# 250100020129x-HW-V2_2.net
KiCad netlist of a schematic drawn in EAGLE
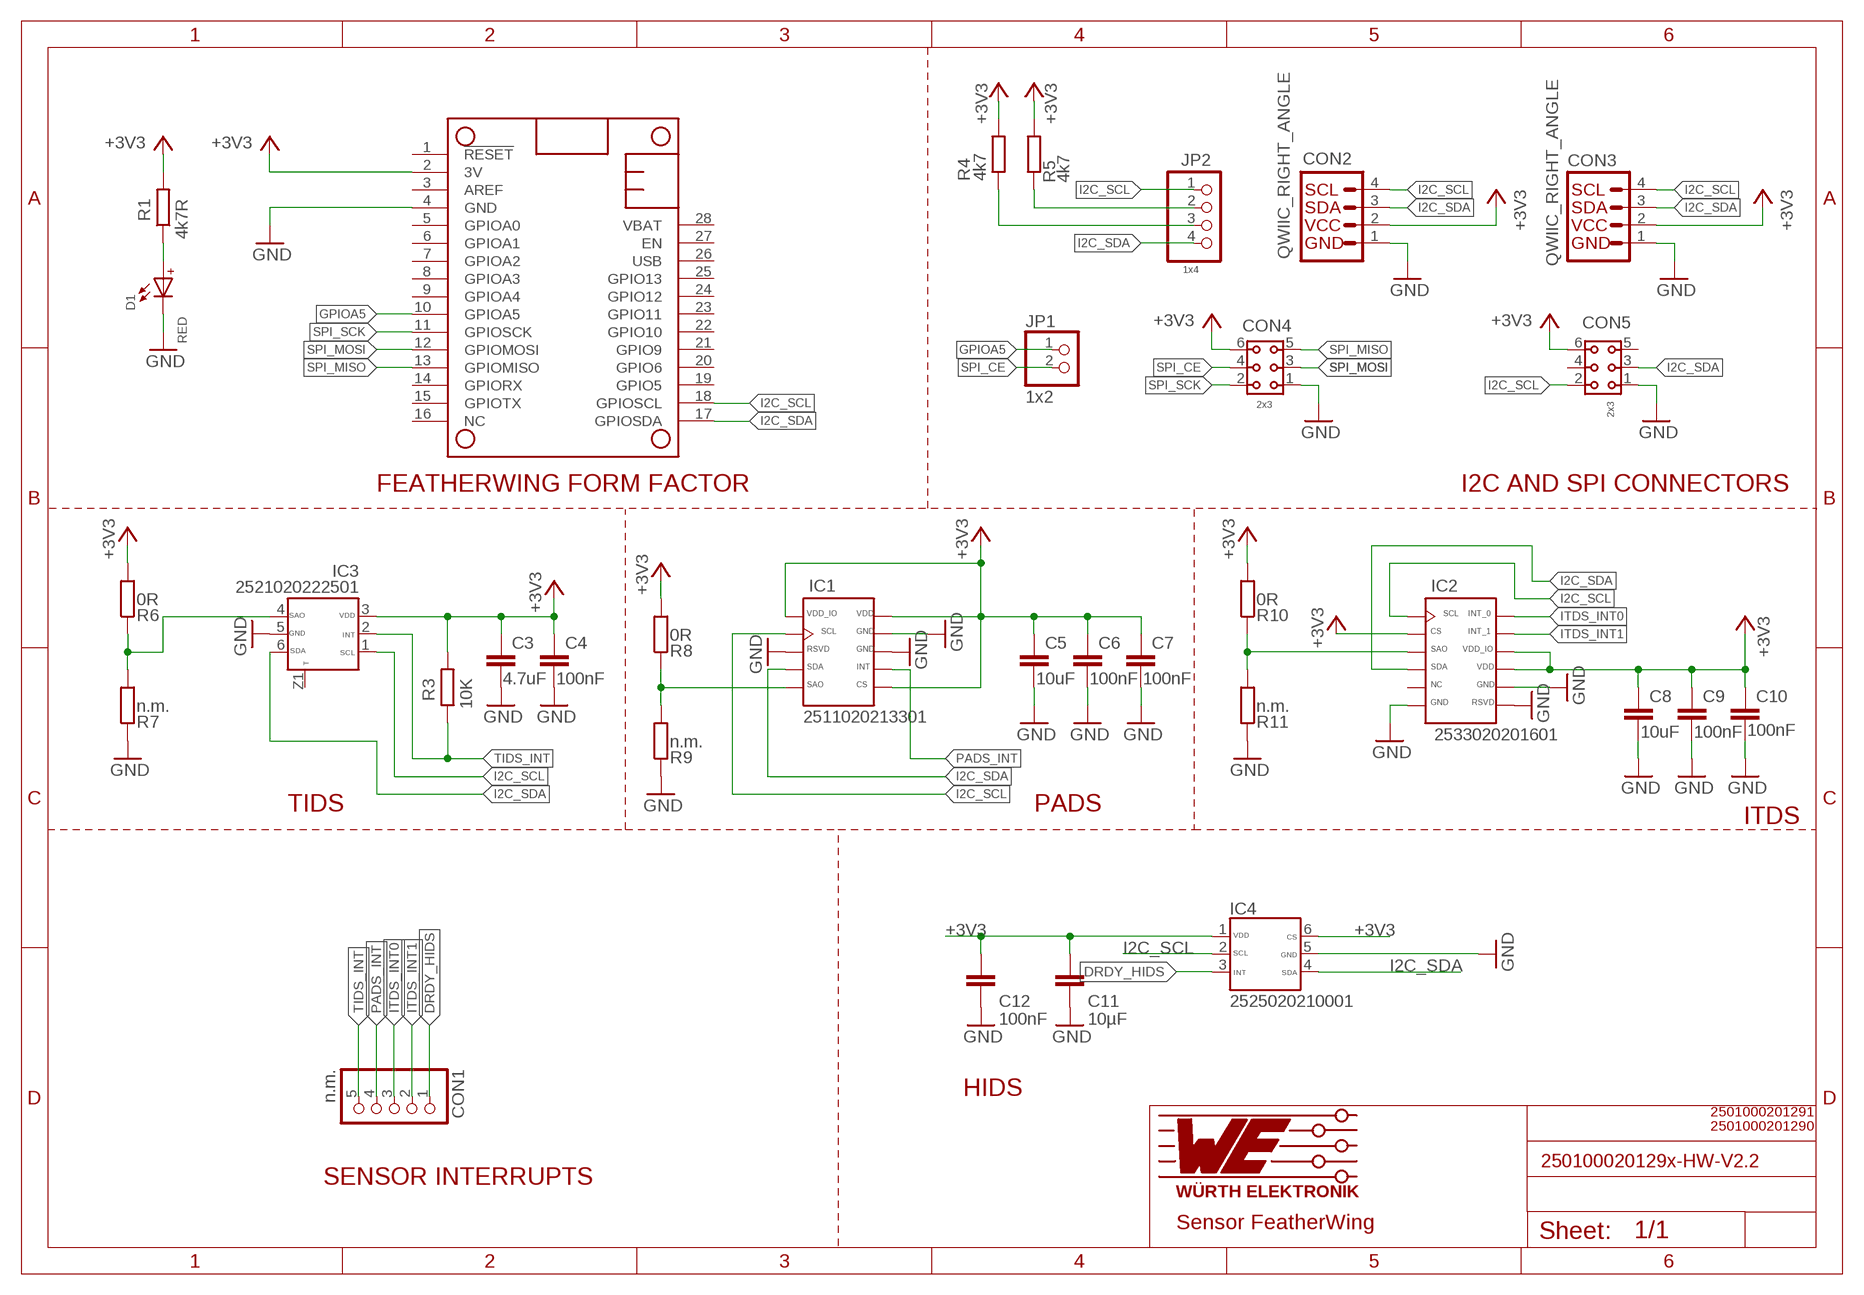
[diagram p0: schematic, sheet 1]

(export (version "E")
  (design (tool "Eeschema 10.0.6"))
  (components
    (comp (ref "C3")
      (value "4.7uF")
      (footprint "eagle-import:C0402_IPC")
      (fields (field (name "MANUFACTURER") "Murata"))
      (libsource (lib "eagle-import") (part "C0402_IPC4,7UF"))
    )
    (comp (ref "C4")
      (value "100nF")
      (footprint "eagle-import:C0402_IPC")
      (fields (field (name "MANUFACTURER") "Yageo"))
      (libsource (lib "eagle-import") (part "C0402_IPC100NF"))
    )
    (comp (ref "C5")
      (value "10uF")
      (footprint "eagle-import:C0402_IPC")
      (fields (field (name "MANUFACTURER") "Murata"))
      (libsource (lib "eagle-import") (part "C0402_IPC10UF"))
    )
    (comp (ref "C6")
      (value "100nF")
      (footprint "eagle-import:C0402_IPC")
      (fields (field (name "MANUFACTURER") "Yageo"))
      (libsource (lib "eagle-import") (part "C0402_IPC100NF"))
    )
    (comp (ref "C7")
      (value "100nF")
      (footprint "eagle-import:C0402_IPC")
      (fields (field (name "MANUFACTURER") "Yageo"))
      (libsource (lib "eagle-import") (part "C0402_IPC100NF"))
    )
    (comp (ref "C8")
      (value "10uF")
      (footprint "eagle-import:C0402_IPC")
      (fields (field (name "MANUFACTURER") "Murata"))
      (libsource (lib "eagle-import") (part "C0402_IPC10UF"))
    )
    (comp (ref "C9")
      (value "100nF")
      (footprint "eagle-import:C0402_IPC")
      (fields (field (name "MANUFACTURER") "Yageo"))
      (libsource (lib "eagle-import") (part "C0402_IPC100NF"))
    )
    (comp (ref "C10")
      (value "100nF")
      (footprint "eagle-import:C0402_IPC")
      (fields (field (name "MANUFACTURER") "Yageo"))
      (libsource (lib "eagle-import") (part "C0402_IPC100NF"))
    )
    (comp (ref "C11")
      (value "10µF")
      (footprint "eagle-import:C0402_IPC")
      (fields (field (name "MANUFACTURER") "Murata"))
      (libsource (lib "eagle-import") (part "C0402_IPC10UF"))
    )
    (comp (ref "C12")
      (value "100nF")
      (footprint "eagle-import:C0402_IPC")
      (fields (field (name "MANUFACTURER") "Yageo"))
      (libsource (lib "eagle-import") (part "C0402_IPC100NF"))
    )
    (comp (ref "CON1")
      (value "n.m.")
      (footprint "eagle-import:1X05_R")
      (fields (field (name "MANUFACTURER") "Würth Elektronik"))
      (libsource (lib "eagle-import") (part "PINHD-1X5/R"))
    )
    (comp (ref "CON2")
      (value "QWIIC_RIGHT_ANGLE")
      (footprint "eagle-import:JST04_1MM_RA")
      (fields (field (name "MANUFACTURER") "JST"))
      (libsource (lib "eagle-import") (part "QWIIC_CONNECTORJS-1MM"))
    )
    (comp (ref "CON3")
      (value "QWIIC_RIGHT_ANGLE")
      (footprint "eagle-import:JST04_1MM_RA")
      (fields (field (name "MANUFACTURER") "JST"))
      (libsource (lib "eagle-import") (part "QWIIC_CONNECTORJS-1MM"))
    )
    (comp (ref "CON4")
      (value "2x3")
      (footprint "eagle-import:613006243121")
      (fields (field (name "MANUFACTURER") "Würth Elektronik") (field (name "COMMENT") "Stick out of PCB"))
      (libsource (lib "eagle-import") (part "6130XX243121_613006243121"))
    )
    (comp (ref "CON5")
      (value "2x3")
      (footprint "eagle-import:613006243121")
      (fields (field (name "MANUFACTURER") "Würth Elektronik") (field (name "COMMENT") "Stick out of PCB"))
      (libsource (lib "eagle-import") (part "6130XX243121_613006243121"))
    )
    (comp (ref "D1")
      (value "RED")
      (footprint "eagle-import:WL-SMSW_1204_A")
      (fields (field (name "MANUFACTURER") "Würth Elektronik"))
      (libsource (lib "eagle-import") (part "WL-SMSW_1204_155124VS73200"))
    )
    (comp (ref "IC1")
      (value "2511020213301")
      (footprint "eagle-import:WSEN-PADS_2511020213301")
      (fields (field (name "MANUFACTURER") "Würth Elektronik"))
      (libsource (lib "eagle-import") (part "WSEN-PADS_2511020213301"))
    )
    (comp (ref "IC2")
      (value "2533020201601")
      (footprint "eagle-import:WSEN-ITDS_2533020201601")
      (fields (field (name "MANUFACTURER") "Würth Elektronik"))
      (libsource (lib "eagle-import") (part "WSEN-ITDS_2533020201601"))
    )
    (comp (ref "IC3")
      (value "2521020222501")
      (footprint "eagle-import:WSEN-TIDS_2521020222501")
      (fields (field (name "MANUFACTURER") "Würth Elektronik"))
      (libsource (lib "eagle-import") (part "WSEN-TIDS_2521020222501"))
    )
    (comp (ref "IC4")
      (value "2525020210001")
      (footprint "eagle-import:WSEN-HIDS_2525020210001")
      (fields (field (name "MANUFACTURER") "Würth Elektronik") (field (name "HEIGHT") "1.0mm"))
      (libsource (lib "eagle-import") (part "WSEN-HIDS_2525020210001"))
    )
    (comp (ref "JP1")
      (value "1x2")
      (footprint "eagle-import:1X02_R")
      (fields (field (name "MANUFACTURER") "Würth Elektronik"))
      (libsource (lib "eagle-import") (part "PINHD-1X2/R"))
    )
    (comp (ref "JP2")
      (value "1x4")
      (footprint "eagle-import:1X04_R")
      (fields (field (name "COMMENT") "2xJumper, 1-2, 3-4") (field (name "MANUFACTURER") "Würth Elektronik"))
      (libsource (lib "eagle-import") (part "PINHD-1X4/R"))
    )
    (comp (ref "MS1")
      (value "FEATHERWING")
      (footprint "eagle-import:FEATHERWING")
      (fields
        (field (name "COMMENT") "header: 1 x 12 & 1 x 16, stackup, pins clean")
        (field (name "MANUFACTURER") "Adafruit")
      )
      (libsource (lib "eagle-import") (part "FEATHERWING"))
    )
    (comp (ref "R1")
      (value "4k7R")
      (footprint "eagle-import:R0402_IPC")
      (fields (field (name "MANUFACTURER") "Yageo"))
      (libsource (lib "eagle-import") (part "R0402_IPC4K7"))
    )
    (comp (ref "R3")
      (value "10K")
      (footprint "eagle-import:R0402_IPC")
      (fields (field (name "MANUFACTURER") "Yageo"))
      (libsource (lib "eagle-import") (part "R0402_IPC10KR"))
    )
    (comp (ref "R4")
      (value "4k7")
      (footprint "eagle-import:R0402_IPC")
      (fields (field (name "MANUFACTURER") "Yageo"))
      (libsource (lib "eagle-import") (part "R0402_IPC4K7"))
    )
    (comp (ref "R5")
      (value "4k7")
      (footprint "eagle-import:R0402_IPC")
      (fields (field (name "MANUFACTURER") "Yageo"))
      (libsource (lib "eagle-import") (part "R0402_IPC4K7"))
    )
    (comp (ref "R6")
      (value "0R")
      (footprint "eagle-import:R0402_IPC")
      (fields (field (name "MANUFACTURER") "Yageo"))
      (libsource (lib "eagle-import") (part "R0402_IPC0R"))
    )
    (comp (ref "R7")
      (value "n.m.")
      (footprint "eagle-import:R0402_IPC")
      (fields (field (name "MANUFACTURER") "Yageo"))
      (libsource (lib "eagle-import") (part "R0402_IPC"))
    )
    (comp (ref "R8")
      (value "0R")
      (footprint "eagle-import:R0402_IPC")
      (fields (field (name "MANUFACTURER") "Yageo"))
      (libsource (lib "eagle-import") (part "R0402_IPC0R"))
    )
    (comp (ref "R9")
      (value "n.m.")
      (footprint "eagle-import:R0402_IPC")
      (fields (field (name "MANUFACTURER") "Yageo"))
      (libsource (lib "eagle-import") (part "R0402_IPC"))
    )
    (comp (ref "R10")
      (value "0R")
      (footprint "eagle-import:R0402_IPC")
      (fields (field (name "MANUFACTURER") "Yageo"))
      (libsource (lib "eagle-import") (part "R0402_IPC0R"))
    )
    (comp (ref "R11")
      (value "n.m.")
      (footprint "eagle-import:R0402_IPC")
      (fields (field (name "MANUFACTURER") "Yageo"))
      (libsource (lib "eagle-import") (part "R0402_IPC"))
    )
  )
  (nets
    (net (code "1") (name "+3V3") (class "Default")
      (node (ref "C10") (pin "1") (pinfunction "1_1") (pintype "passive"))
      (node (ref "C11") (pin "2") (pinfunction "2_2") (pintype "passive"))
      (node (ref "C12") (pin "2") (pinfunction "2_2") (pintype "passive"))
      (node (ref "C3") (pin "1") (pinfunction "1_1") (pintype "passive"))
      (node (ref "C4") (pin "1") (pinfunction "1_1") (pintype "passive"))
      (node (ref "C5") (pin "1") (pinfunction "1_1") (pintype "passive"))
      (node (ref "C6") (pin "1") (pinfunction "1_1") (pintype "passive"))
      (node (ref "C7") (pin "1") (pinfunction "1_1") (pintype "passive"))
      (node (ref "C8") (pin "1") (pinfunction "1_1") (pintype "passive"))
      (node (ref "C9") (pin "1") (pinfunction "1_1") (pintype "passive"))
      (node (ref "CON2") (pin "2") (pinfunction "2_2") (pintype "power_in"))
      (node (ref "CON3") (pin "2") (pinfunction "2_2") (pintype "power_in"))
      (node (ref "CON4") (pin "6") (pinfunction "6_6") (pintype "passive"))
      (node (ref "CON5") (pin "6") (pinfunction "6_6") (pintype "passive"))
      (node (ref "IC1") (pin "1") (pinfunction "VDD_IO_1") (pintype "power_in"))
      (node (ref "IC1") (pin "10") (pinfunction "VDD_10") (pintype "power_in"))
      (node (ref "IC1") (pin "6") (pinfunction "CS_6") (pintype "input"))
      (node (ref "IC2") (pin "10") (pinfunction "VDD_IO_10") (pintype "power_in"))
      (node (ref "IC2") (pin "2") (pinfunction "CS_2") (pintype "input"))
      (node (ref "IC2") (pin "9") (pinfunction "VDD_9") (pintype "power_in"))
      (node (ref "IC3") (pin "3") (pinfunction "VDD_3") (pintype "power_in"))
      (node (ref "IC4") (pin "1") (pinfunction "VDD_1") (pintype "power_in"))
      (node (ref "IC4") (pin "6") (pinfunction "CS_6") (pintype "passive"))
      (node (ref "MS1") (pin "2") (pinfunction "3V_2") (pintype "power_in"))
      (node (ref "R1") (pin "2") (pinfunction "2_2") (pintype "passive"))
      (node (ref "R10") (pin "2") (pinfunction "2_2") (pintype "passive"))
      (node (ref "R3") (pin "2") (pinfunction "2_2") (pintype "passive"))
      (node (ref "R4") (pin "2") (pinfunction "2_2") (pintype "passive"))
      (node (ref "R5") (pin "2") (pinfunction "2_2") (pintype "passive"))
      (node (ref "R6") (pin "2") (pinfunction "2_2") (pintype "passive"))
      (node (ref "R8") (pin "2") (pinfunction "2_2") (pintype "passive"))
    )
    (net (code "2") (name "/USB") (class "Default")
      (node (ref "MS1") (pin "26") (pinfunction "USB_26") (pintype "power_in"))
    )
    (net (code "3") (name "/VBAT") (class "Default")
      (node (ref "MS1") (pin "28") (pinfunction "VBAT_28") (pintype "power_in"))
    )
    (net (code "4") (name "DRDY_HIDS") (class "Default")
      (node (ref "CON1") (pin "1") (pinfunction "1_1") (pintype "passive"))
      (node (ref "IC4") (pin "3") (pinfunction "INT_3") (pintype "output"))
    )
    (net (code "5") (name "GND") (class "Default")
      (node (ref "C10") (pin "2") (pinfunction "2_2") (pintype "passive"))
      (node (ref "C11") (pin "1") (pinfunction "1_1") (pintype "passive"))
      (node (ref "C12") (pin "1") (pinfunction "1_1") (pintype "passive"))
      (node (ref "C3") (pin "2") (pinfunction "2_2") (pintype "passive"))
      (node (ref "C4") (pin "2") (pinfunction "2_2") (pintype "passive"))
      (node (ref "C5") (pin "2") (pinfunction "2_2") (pintype "passive"))
      (node (ref "C6") (pin "2") (pinfunction "2_2") (pintype "passive"))
      (node (ref "C7") (pin "2") (pinfunction "2_2") (pintype "passive"))
      (node (ref "C8") (pin "2") (pinfunction "2_2") (pintype "passive"))
      (node (ref "C9") (pin "2") (pinfunction "2_2") (pintype "passive"))
      (node (ref "CON2") (pin "1") (pinfunction "1_1") (pintype "power_in"))
      (node (ref "CON3") (pin "1") (pinfunction "1_1") (pintype "power_in"))
      (node (ref "CON4") (pin "1") (pinfunction "1_1") (pintype "passive"))
      (node (ref "CON5") (pin "1") (pinfunction "1_1") (pintype "passive"))
      (node (ref "D1") (pin "1") (pinfunction "-_1") (pintype "passive"))
      (node (ref "IC1") (pin "3") (pinfunction "RSVD_3") (pintype "bidirectional"))
      (node (ref "IC1") (pin "8") (pinfunction "GND_8") (pintype "power_in"))
      (node (ref "IC1") (pin "9") (pinfunction "GND_9") (pintype "power_in"))
      (node (ref "IC2") (pin "6") (pinfunction "GND_6") (pintype "power_in"))
      (node (ref "IC2") (pin "7") (pinfunction "RSVD_7") (pintype "bidirectional"))
      (node (ref "IC2") (pin "8") (pinfunction "GND_8") (pintype "power_in"))
      (node (ref "IC3") (pin "5") (pinfunction "GND_5") (pintype "power_in"))
      (node (ref "IC4") (pin "5") (pinfunction "GND_5") (pintype "power_in"))
      (node (ref "MS1") (pin "4") (pinfunction "GND_4") (pintype "power_in"))
      (node (ref "R11") (pin "1") (pinfunction "1_1") (pintype "passive"))
      (node (ref "R7") (pin "1") (pinfunction "1_1") (pintype "passive"))
      (node (ref "R9") (pin "1") (pinfunction "1_1") (pintype "passive"))
    )
    (net (code "6") (name "GPIOA5") (class "Default")
      (node (ref "JP1") (pin "1") (pinfunction "1_1") (pintype "passive"))
      (node (ref "MS1") (pin "10") (pinfunction "GPIOA5_10") (pintype "bidirectional"))
    )
    (net (code "7") (name "I2C_SCL") (class "Default")
      (node (ref "CON2") (pin "4") (pinfunction "4_4") (pintype "passive"))
      (node (ref "CON3") (pin "4") (pinfunction "4_4") (pintype "passive"))
      (node (ref "CON5") (pin "2") (pinfunction "2_2") (pintype "passive"))
      (node (ref "IC1") (pin "2") (pinfunction "SCL_2") (pintype "input"))
      (node (ref "IC2") (pin "1") (pinfunction "SCL_1") (pintype "input"))
      (node (ref "IC3") (pin "1") (pinfunction "SCL_1") (pintype "bidirectional"))
      (node (ref "IC4") (pin "2") (pinfunction "SCL_2") (pintype "bidirectional"))
      (node (ref "JP2") (pin "1") (pinfunction "1_1") (pintype "passive"))
      (node (ref "MS1") (pin "18") (pinfunction "GPIOSCL_18") (pintype "bidirectional"))
    )
    (net (code "8") (name "I2C_SDA") (class "Default")
      (node (ref "CON2") (pin "3") (pinfunction "3_3") (pintype "passive"))
      (node (ref "CON3") (pin "3") (pinfunction "3_3") (pintype "passive"))
      (node (ref "CON5") (pin "3") (pinfunction "3_3") (pintype "passive"))
      (node (ref "IC1") (pin "4") (pinfunction "SDA_4") (pintype "bidirectional"))
      (node (ref "IC2") (pin "4") (pinfunction "SDA_4") (pintype "bidirectional"))
      (node (ref "IC3") (pin "6") (pinfunction "SDA_6") (pintype "bidirectional"))
      (node (ref "IC4") (pin "4") (pinfunction "SDA_4") (pintype "bidirectional"))
      (node (ref "JP2") (pin "4") (pinfunction "4_4") (pintype "passive"))
      (node (ref "MS1") (pin "17") (pinfunction "GPIOSDA_17") (pintype "bidirectional"))
    )
    (net (code "9") (name "ITDS_INT0") (class "Default")
      (node (ref "CON1") (pin "3") (pinfunction "3_3") (pintype "passive"))
      (node (ref "IC2") (pin "12") (pinfunction "INT_0_12") (pintype "output"))
    )
    (net (code "10") (name "ITDS_INT1") (class "Default")
      (node (ref "CON1") (pin "2") (pinfunction "2_2") (pintype "passive"))
      (node (ref "IC2") (pin "11") (pinfunction "INT_1_11") (pintype "bidirectional"))
    )
    (net (code "11") (name "Net-(D1-+)") (class "Default")
      (node (ref "D1") (pin "2") (pinfunction "+_2") (pintype "passive"))
      (node (ref "R1") (pin "1") (pinfunction "1_1") (pintype "passive"))
    )
    (net (code "12") (name "Net-(IC1-SAO)") (class "Default")
      (node (ref "IC1") (pin "5") (pinfunction "SAO_5") (pintype "bidirectional"))
      (node (ref "R8") (pin "1") (pinfunction "1_1") (pintype "passive"))
      (node (ref "R9") (pin "2") (pinfunction "2_2") (pintype "passive"))
    )
    (net (code "13") (name "Net-(IC2-SAO)") (class "Default")
      (node (ref "IC2") (pin "3") (pinfunction "SAO_3") (pintype "bidirectional"))
      (node (ref "R10") (pin "1") (pinfunction "1_1") (pintype "passive"))
      (node (ref "R11") (pin "2") (pinfunction "2_2") (pintype "passive"))
    )
    (net (code "14") (name "Net-(IC3-SAO)") (class "Default")
      (node (ref "IC3") (pin "4") (pinfunction "SAO_4") (pintype "bidirectional"))
      (node (ref "R6") (pin "1") (pinfunction "1_1") (pintype "passive"))
      (node (ref "R7") (pin "2") (pinfunction "2_2") (pintype "passive"))
    )
    (net (code "15") (name "Net-(JP2-Pad2)") (class "Default")
      (node (ref "JP2") (pin "2") (pinfunction "2_2") (pintype "passive"))
      (node (ref "R5") (pin "1") (pinfunction "1_1") (pintype "passive"))
    )
    (net (code "16") (name "Net-(JP2-Pad3)") (class "Default")
      (node (ref "JP2") (pin "3") (pinfunction "3_3") (pintype "passive"))
      (node (ref "R4") (pin "1") (pinfunction "1_1") (pintype "passive"))
    )
    (net (code "17") (name "PADS_INT") (class "Default")
      (node (ref "CON1") (pin "4") (pinfunction "4_4") (pintype "passive"))
      (node (ref "IC1") (pin "7") (pinfunction "INT_7") (pintype "output"))
    )
    (net (code "18") (name "SPI_CE") (class "Default")
      (node (ref "CON4") (pin "4") (pinfunction "4_4") (pintype "passive"))
      (node (ref "JP1") (pin "2") (pinfunction "2_2") (pintype "passive"))
    )
    (net (code "19") (name "SPI_MISO") (class "Default")
      (node (ref "CON4") (pin "5") (pinfunction "5_5") (pintype "passive"))
      (node (ref "MS1") (pin "13") (pinfunction "GPIOMISO_13") (pintype "bidirectional"))
    )
    (net (code "20") (name "SPI_MOSI") (class "Default")
      (node (ref "CON4") (pin "3") (pinfunction "3_3") (pintype "passive"))
      (node (ref "MS1") (pin "12") (pinfunction "GPIOMOSI_12") (pintype "bidirectional"))
    )
    (net (code "21") (name "SPI_SCK") (class "Default")
      (node (ref "CON4") (pin "2") (pinfunction "2_2") (pintype "passive"))
      (node (ref "MS1") (pin "11") (pinfunction "GPIOSCK_11") (pintype "bidirectional"))
    )
    (net (code "22") (name "TIDS_INT") (class "Default")
      (node (ref "CON1") (pin "5") (pinfunction "5_5") (pintype "passive"))
      (node (ref "IC3") (pin "2") (pinfunction "INT_2") (pintype "bidirectional"))
      (node (ref "R3") (pin "1") (pinfunction "1_1") (pintype "passive"))
    )
    (net (code "23") (name "unconnected-(CON5-Pad4)") (class "Default")
      (node (ref "CON5") (pin "4") (pinfunction "4_4") (pintype "passive"))
    )
    (net (code "24") (name "unconnected-(CON5-Pad5)") (class "Default")
      (node (ref "CON5") (pin "5") (pinfunction "5_5") (pintype "passive"))
    )
    (net (code "25") (name "unconnected-(IC2-NC-Pad5)") (class "Default")
      (node (ref "IC2") (pin "5") (pinfunction "NC_5") (pintype "no_connect"))
    )
    (net (code "26") (name "unconnected-(IC3-P$1-PadZ1)") (class "Default")
      (node (ref "IC3") (pin "Z1") (pinfunction "P$1_Z1") (pintype "bidirectional"))
    )
    (net (code "27") (name "unconnected-(MS1-AREF-Pad3)") (class "Default")
      (node (ref "MS1") (pin "3") (pinfunction "AREF_3") (pintype "passive"))
    )
    (net (code "28") (name "unconnected-(MS1-EN-Pad27)") (class "Default")
      (node (ref "MS1") (pin "27") (pinfunction "EN_27") (pintype "passive"))
    )
    (net (code "29") (name "unconnected-(MS1-GPIO5-Pad19)") (class "Default")
      (node (ref "MS1") (pin "19") (pinfunction "GPIO5_19") (pintype "bidirectional"))
    )
    (net (code "30") (name "unconnected-(MS1-GPIO6-Pad20)") (class "Default")
      (node (ref "MS1") (pin "20") (pinfunction "GPIO6_20") (pintype "bidirectional"))
    )
    (net (code "31") (name "unconnected-(MS1-GPIO9-Pad21)") (class "Default")
      (node (ref "MS1") (pin "21") (pinfunction "GPIO9_21") (pintype "bidirectional"))
    )
    (net (code "32") (name "unconnected-(MS1-GPIO10-Pad22)") (class "Default")
      (node (ref "MS1") (pin "22") (pinfunction "GPIO10_22") (pintype "bidirectional"))
    )
    (net (code "33") (name "unconnected-(MS1-GPIO11-Pad23)") (class "Default")
      (node (ref "MS1") (pin "23") (pinfunction "GPIO11_23") (pintype "bidirectional"))
    )
    (net (code "34") (name "unconnected-(MS1-GPIO12-Pad24)") (class "Default")
      (node (ref "MS1") (pin "24") (pinfunction "GPIO12_24") (pintype "bidirectional"))
    )
    (net (code "35") (name "unconnected-(MS1-GPIO13-Pad25)") (class "Default")
      (node (ref "MS1") (pin "25") (pinfunction "GPIO13_25") (pintype "bidirectional"))
    )
    (net (code "36") (name "unconnected-(MS1-GPIOA0-Pad5)") (class "Default")
      (node (ref "MS1") (pin "5") (pinfunction "GPIOA0_5") (pintype "bidirectional"))
    )
    (net (code "37") (name "unconnected-(MS1-GPIOA1-Pad6)") (class "Default")
      (node (ref "MS1") (pin "6") (pinfunction "GPIOA1_6") (pintype "bidirectional"))
    )
    (net (code "38") (name "unconnected-(MS1-GPIOA2-Pad7)") (class "Default")
      (node (ref "MS1") (pin "7") (pinfunction "GPIOA2_7") (pintype "bidirectional"))
    )
    (net (code "39") (name "unconnected-(MS1-GPIOA3-Pad8)") (class "Default")
      (node (ref "MS1") (pin "8") (pinfunction "GPIOA3_8") (pintype "bidirectional"))
    )
    (net (code "40") (name "unconnected-(MS1-GPIOA4-Pad9)") (class "Default")
      (node (ref "MS1") (pin "9") (pinfunction "GPIOA4_9") (pintype "bidirectional"))
    )
    (net (code "41") (name "unconnected-(MS1-GPIORX-Pad14)") (class "Default")
      (node (ref "MS1") (pin "14") (pinfunction "GPIORX_14") (pintype "bidirectional"))
    )
    (net (code "42") (name "unconnected-(MS1-GPIOTX-Pad15)") (class "Default")
      (node (ref "MS1") (pin "15") (pinfunction "GPIOTX_15") (pintype "bidirectional"))
    )
    (net (code "43") (name "unconnected-(MS1-NC-Pad16)") (class "Default")
      (node (ref "MS1") (pin "16") (pinfunction "NC_16") (pintype "passive"))
    )
    (net (code "44") (name "unconnected-(MS1-~{RESET}-Pad1)") (class "Default")
      (node (ref "MS1") (pin "1") (pinfunction "~{RESET}_1") (pintype "input"))
    )
  )
)
